# EEPROM.net
KiCad netlist of a schematic drawn in Altium Designer
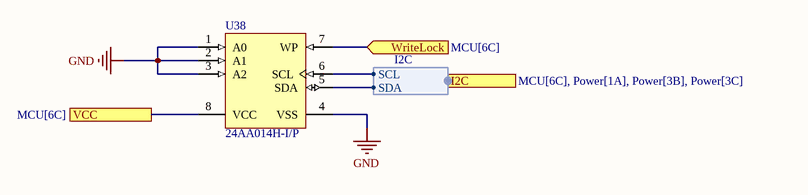
[diagram p0: EEPROM.SchDoc]

(export (version "E")
  (design (tool "Eeschema 10.0.6"))
  (components
    (comp (ref "U38")
      (value "24AA014H-I/P")
      (footprint "PDIP300-P8")
      (description "1Kbit, 400kHz, 1.7V, I2C Addressable Serial EEPROM, 8-Pin PDIP, Industrial Temperature")
      (libsource (lib "Altium Content Vault") (part "MEM-SEEPROM-34AA02-IL8"))
    )
  )
  (nets
    (net (code "2") (name "/SCL") (class "Default")
      (node (ref "U38") (pin "6") (pinfunction "SCL_6") (pintype "input"))
    )
    (net (code "3") (name "/SDA") (class "Default")
      (node (ref "U38") (pin "5") (pinfunction "SDA_5") (pintype "bidirectional"))
    )
    (net (code "4") (name "/VCC") (class "Default")
      (node (ref "U38") (pin "8") (pinfunction "VCC_8") (pintype "power_in"))
    )
    (net (code "5") (name "/WriteLock") (class "Default")
      (node (ref "U38") (pin "7") (pinfunction "WP_7") (pintype "input"))
    )
    (net (code "7") (name "GND") (class "Default")
      (node (ref "U38") (pin "1") (pinfunction "A0_1") (pintype "input"))
      (node (ref "U38") (pin "2") (pinfunction "A1_2") (pintype "input"))
      (node (ref "U38") (pin "3") (pinfunction "A2_3") (pintype "input"))
      (node (ref "U38") (pin "4") (pinfunction "VSS_4") (pintype "power_in"))
    )
  )
)
